# relay_board.net
KiCad netlist of a schematic drawn in EAGLE
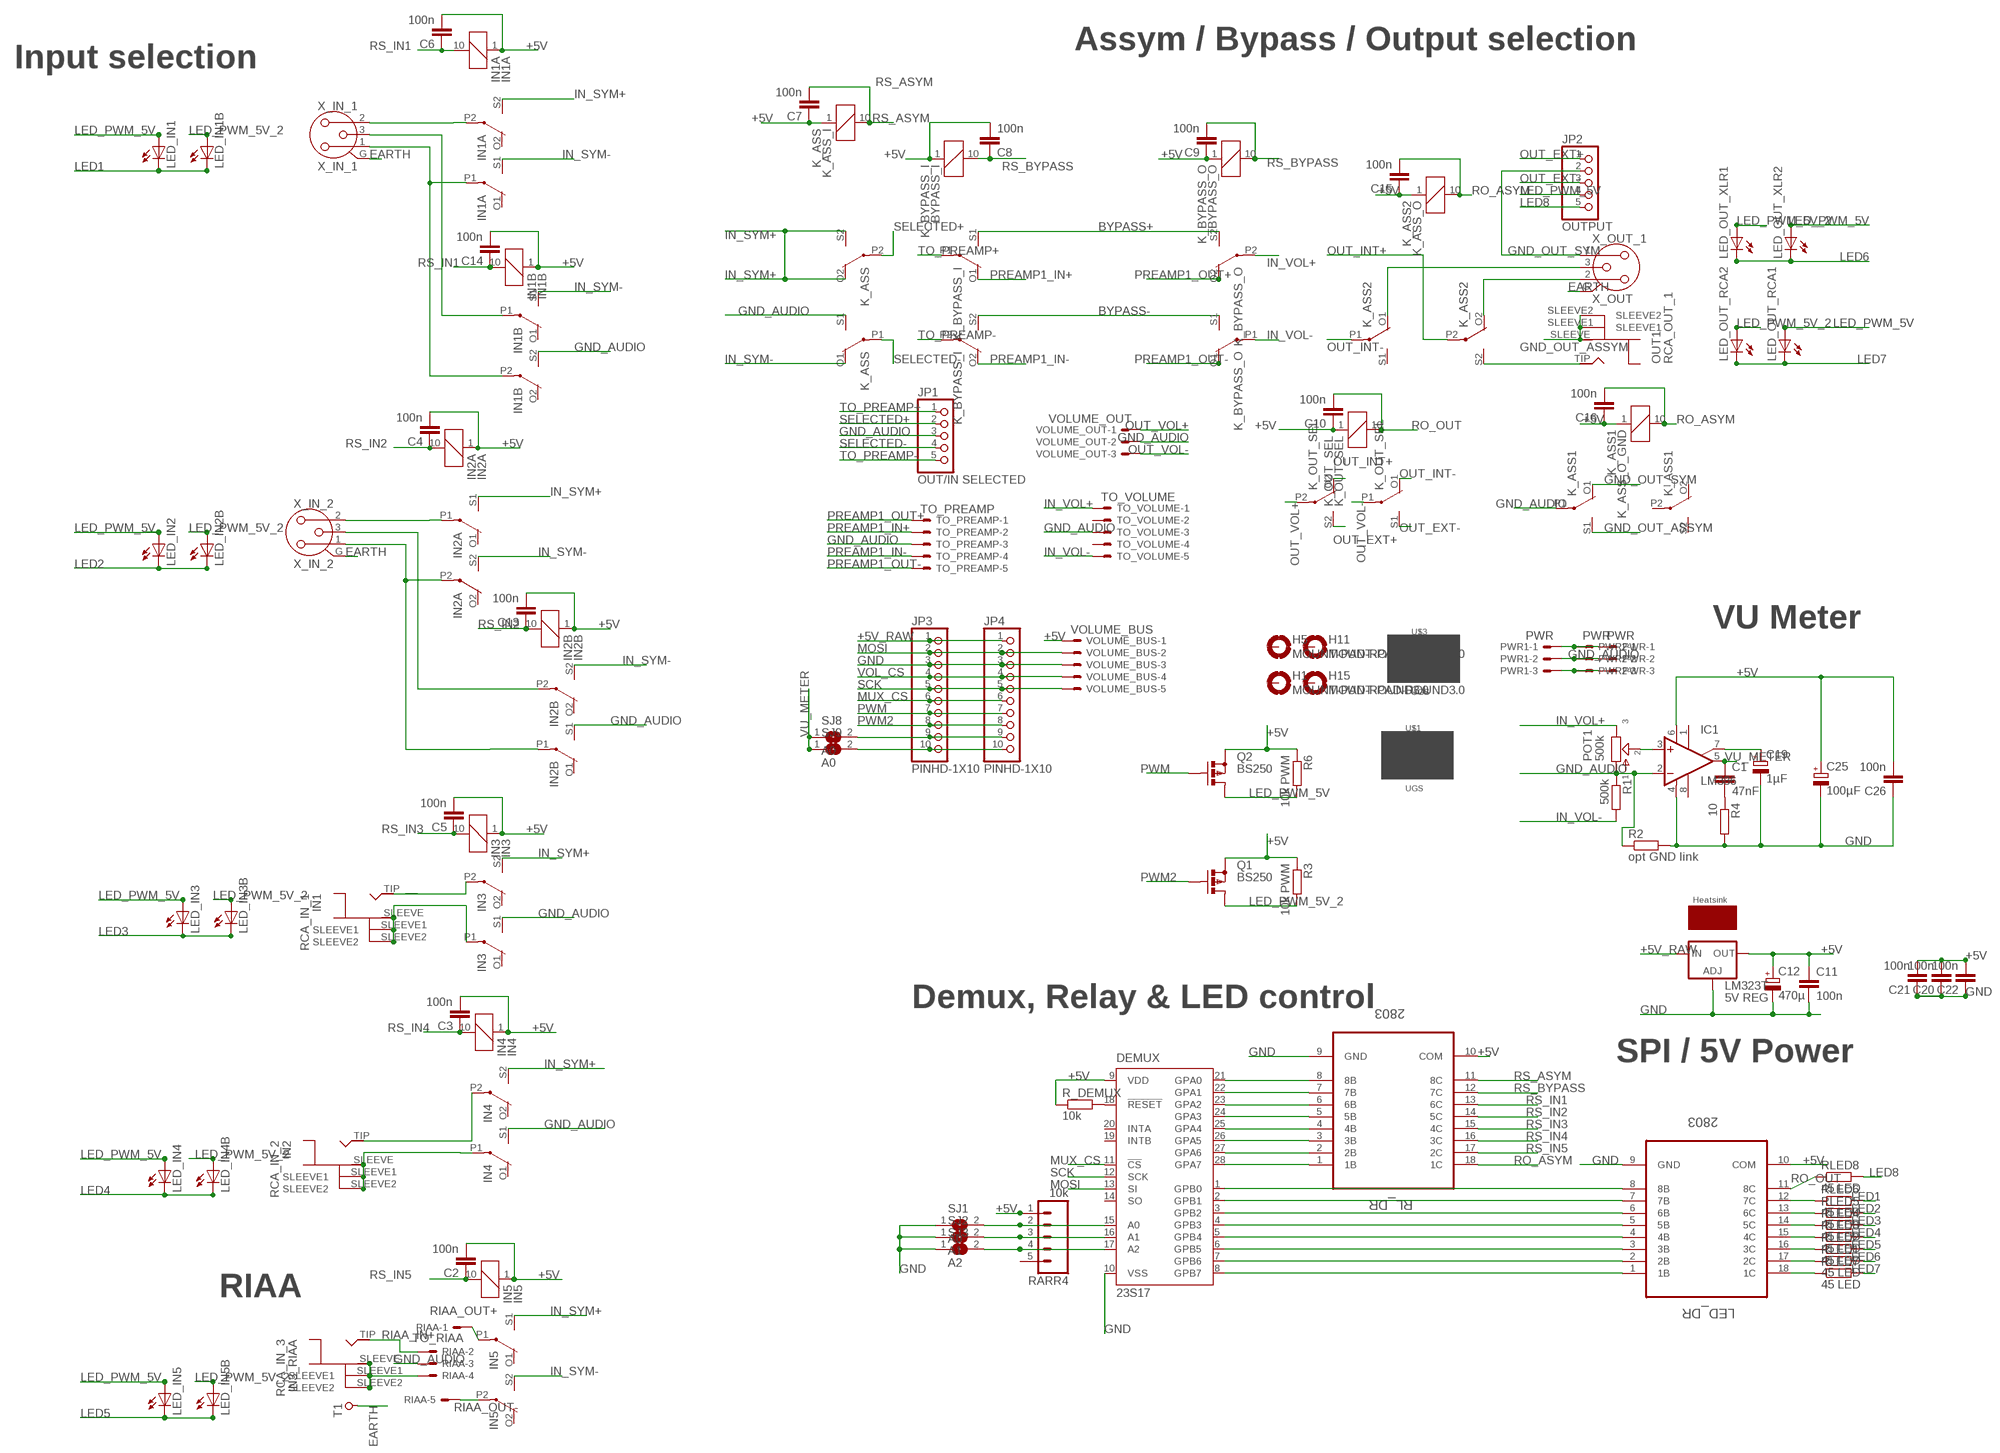
[diagram p0: schematic, sheet 1]

(export (version "E")
  (design (tool "Eeschema 10.0.6"))
  (components
    (comp (ref "C1")
      (value "47nF")
      (footprint "eagle-import:C5B3")
      (libsource (lib "eagle-import") (part "C5/3"))
    )
    (comp (ref "C2")
      (value "100n")
      (footprint "eagle-import:C050-025X075")
      (libsource (lib "eagle-import") (part "C-EU050-025X075"))
    )
    (comp (ref "C3")
      (value "100n")
      (footprint "eagle-import:C050-025X075")
      (libsource (lib "eagle-import") (part "C-EU050-025X075"))
    )
    (comp (ref "C4")
      (value "100n")
      (footprint "eagle-import:C050-025X075")
      (libsource (lib "eagle-import") (part "C-EU050-025X075"))
    )
    (comp (ref "C5")
      (value "100n")
      (footprint "eagle-import:C050-025X075")
      (libsource (lib "eagle-import") (part "C-EU050-025X075"))
    )
    (comp (ref "C6")
      (value "100n")
      (footprint "eagle-import:C050-025X075")
      (libsource (lib "eagle-import") (part "C-EU050-025X075"))
    )
    (comp (ref "C7")
      (value "100n")
      (footprint "eagle-import:C050-025X075")
      (libsource (lib "eagle-import") (part "C-EU050-025X075"))
    )
    (comp (ref "C8")
      (value "100n")
      (footprint "eagle-import:C050-025X075")
      (libsource (lib "eagle-import") (part "C-EU050-025X075"))
    )
    (comp (ref "C9")
      (value "100n")
      (footprint "eagle-import:C050-025X075")
      (libsource (lib "eagle-import") (part "C-EU050-025X075"))
    )
    (comp (ref "C10")
      (value "100n")
      (footprint "eagle-import:C050-025X075")
      (libsource (lib "eagle-import") (part "C-EU050-025X075"))
    )
    (comp (ref "C11")
      (value "100n")
      (footprint "eagle-import:C050-025X075")
      (libsource (lib "eagle-import") (part "C-EU050-025X075"))
    )
    (comp (ref "C12")
      (value "470µ")
      (footprint "eagle-import:E2,5-6")
      (libsource (lib "eagle-import") (part "CPOL-EUE2.5-6"))
    )
    (comp (ref "C13")
      (value "100n")
      (footprint "eagle-import:C050-025X075")
      (libsource (lib "eagle-import") (part "C-EU050-025X075"))
    )
    (comp (ref "C14")
      (value "100n")
      (footprint "eagle-import:C050-025X075")
      (libsource (lib "eagle-import") (part "C-EU050-025X075"))
    )
    (comp (ref "C15")
      (value "100n")
      (footprint "eagle-import:C050-025X075")
      (libsource (lib "eagle-import") (part "C-EU050-025X075"))
    )
    (comp (ref "C16")
      (value "100n")
      (footprint "eagle-import:C050-025X075")
      (libsource (lib "eagle-import") (part "C-EU050-025X075"))
    )
    (comp (ref "C19")
      (value "1µF")
      (footprint "eagle-import:E2,5-5")
      (libsource (lib "eagle-import") (part "CPOL-EUE2.5-5"))
    )
    (comp (ref "C20")
      (value "100n")
      (footprint "eagle-import:C050-025X075")
      (libsource (lib "eagle-import") (part "C-EU050-025X075"))
    )
    (comp (ref "C21")
      (value "100n")
      (footprint "eagle-import:C050-025X075")
      (libsource (lib "eagle-import") (part "C-EU050-025X075"))
    )
    (comp (ref "C22")
      (value "100n")
      (footprint "eagle-import:C050-025X075")
      (libsource (lib "eagle-import") (part "C-EU050-025X075"))
    )
    (comp (ref "C25")
      (value "100µF")
      (footprint "eagle-import:E5-6")
      (libsource (lib "eagle-import") (part "CPOL-EUE5-6"))
    )
    (comp (ref "C26")
      (value "100n")
      (footprint "eagle-import:C050-025X075")
      (libsource (lib "eagle-import") (part "C-EU050-025X075"))
    )
    (comp (ref "DEMUX")
      (value "23S17")
      (footprint "eagle-import:SO28W")
      (fields
        (field (name "MF") "MICROCHIP")
        (field (name "MPN") "MCP23S17-E/SO")
        (field (name "MPN_1") "MCP23S17-E/SO")
        (field (name "OC_FARNELL") "unknown")
        (field (name "OC_NEWARK") "31K2950")
      )
      (libsource (lib "eagle-import") (part "MCP23S17SO"))
    )
    (comp (ref "H1")
      (value "MOUNT-PAD-ROUND3.0")
      (footprint "eagle-import:3,0-PAD")
      (libsource (lib "eagle-import") (part "MOUNT-PAD-ROUND3.0"))
    )
    (comp (ref "H5")
      (value "MOUNT-PAD-ROUND3.0")
      (footprint "eagle-import:3,0-PAD")
      (libsource (lib "eagle-import") (part "MOUNT-PAD-ROUND3.0"))
    )
    (comp (ref "H11")
      (value "MOUNT-PAD-ROUND3.0")
      (footprint "eagle-import:3,0-PAD")
      (libsource (lib "eagle-import") (part "MOUNT-PAD-ROUND3.0"))
    )
    (comp (ref "H15")
      (value "MOUNT-PAD-ROUND3.0")
      (footprint "eagle-import:3,0-PAD")
      (libsource (lib "eagle-import") (part "MOUNT-PAD-ROUND3.0"))
    )
    (comp (ref "IC1")
      (value "LM386")
      (footprint "eagle-import:DIL08")
      (libsource (lib "eagle-import") (part "LM386"))
    )
    (comp (ref "IN1A")
      (value "IN1A")
      (footprint "eagle-import:G6H2-100")
      (libsource (lib "eagle-import") (part "G6H2-100"))
    )
    (comp (ref "IN1B")
      (value "IN1B")
      (footprint "eagle-import:G6H2-100")
      (fields (field (name "OC_FARNELL") "unknown") (field (name "OC_NEWARK") "unknown"))
      (libsource (lib "eagle-import") (part "G6H2-100"))
    )
    (comp (ref "IN2A")
      (value "IN2A")
      (footprint "eagle-import:G6H2-100")
      (libsource (lib "eagle-import") (part "G6H2-100"))
    )
    (comp (ref "IN2B")
      (value "IN2B")
      (footprint "eagle-import:G6H2-100")
      (fields (field (name "OC_FARNELL") "unknown") (field (name "OC_NEWARK") "unknown"))
      (libsource (lib "eagle-import") (part "G6H2-100"))
    )
    (comp (ref "IN3")
      (value "IN3")
      (footprint "eagle-import:G6H2-100")
      (fields (field (name "OC_FARNELL") "unknown") (field (name "OC_NEWARK") "unknown"))
      (libsource (lib "eagle-import") (part "G6H2-100"))
    )
    (comp (ref "IN4")
      (value "IN4")
      (footprint "eagle-import:G6H2-100")
      (fields (field (name "OC_FARNELL") "unknown") (field (name "OC_NEWARK") "unknown"))
      (libsource (lib "eagle-import") (part "G6H2-100"))
    )
    (comp (ref "IN5")
      (value "IN5")
      (footprint "eagle-import:G6H2-100")
      (libsource (lib "eagle-import") (part "G6H2-100"))
    )
    (comp (ref "JP1")
      (value "OUT/IN SELECTED")
      (footprint "eagle-import:1X05")
      (libsource (lib "eagle-import") (part "PINHD-1X5"))
    )
    (comp (ref "JP2")
      (value "OUTPUT")
      (footprint "eagle-import:1X05")
      (libsource (lib "eagle-import") (part "PINHD-1X5"))
    )
    (comp (ref "JP3")
      (value "PINHD-1X10")
      (footprint "eagle-import:1X10-BIG")
      (libsource (lib "eagle-import") (part "PINHD-1X10"))
    )
    (comp (ref "JP4")
      (value "PINHD-1X10")
      (footprint "eagle-import:1X10-BIG")
      (libsource (lib "eagle-import") (part "PINHD-1X10"))
    )
    (comp (ref "K_ASS")
      (value "K_ASS_I")
      (footprint "eagle-import:G6H2-100")
      (libsource (lib "eagle-import") (part "G6H2-100"))
    )
    (comp (ref "K_ASS1")
      (value "K_ASS_O_GND")
      (footprint "eagle-import:G6H2-100")
      (fields (field (name "OC_FARNELL") "unknown") (field (name "OC_NEWARK") "unknown"))
      (libsource (lib "eagle-import") (part "G6H2-100"))
    )
    (comp (ref "K_ASS2")
      (value "K_ASS_O")
      (footprint "eagle-import:G6H2-100")
      (fields (field (name "OC_FARNELL") "unknown") (field (name "OC_NEWARK") "unknown"))
      (libsource (lib "eagle-import") (part "G6H2-100"))
    )
    (comp (ref "K_BYPASS_I")
      (value "BYPASS_I")
      (footprint "eagle-import:G6H2-100")
      (libsource (lib "eagle-import") (part "G6H2-100"))
    )
    (comp (ref "K_BYPASS_O")
      (value "BYPASS_O")
      (footprint "eagle-import:G6H2-100")
      (libsource (lib "eagle-import") (part "G6H2-100"))
    )
    (comp (ref "K_OUT_SEL")
      (value "K_OUT_SEL")
      (footprint "eagle-import:G6H2-100")
      (fields (field (name "OC_FARNELL") "unknown") (field (name "OC_NEWARK") "unknown"))
      (libsource (lib "eagle-import") (part "G6H2-100"))
    )
    (comp (ref "LED_DR")
      (value "2803")
      (footprint "eagle-import:SOIC127P1030X265-18N")
      (fields
        (field (name "MPN") "ULN2803ADWR")
        (field (name "MPN_1") "ULN2803ADWR")
        (field (name "OC_FARNELL") "1652420")
        (field (name "OC_NEWARK") "87H4769")
        (field (name "PACKAGE") "SOIC-18")
        (field (name "SUPPLIER") "TEXAS INSTRUMENTS")
      )
      (libsource (lib "eagle-import") (part "ULN2803ADWR"))
    )
    (comp (ref "LED_IN1")
      (value "TLLG4400")
      (footprint "eagle-import:LED3MM")
      (fields (field (name "MF") "VISHAY SEMICONDUCTOR"))
      (libsource (lib "eagle-import") (part "TLLG4400"))
    )
    (comp (ref "LED_IN1B")
      (value "TLLG4400")
      (footprint "eagle-import:LED3MM")
      (fields
        (field (name "MF") "VISHAY SEMICONDUCTOR")
        (field (name "MF_1") "VISHAY SEMICONDUCTOR")
        (field (name "OC_FARNELL") "1612435")
      )
      (libsource (lib "eagle-import") (part "TLLG4400"))
    )
    (comp (ref "LED_IN2")
      (value "TLLG4400")
      (footprint "eagle-import:LED3MM")
      (fields (field (name "MF") "VISHAY SEMICONDUCTOR"))
      (libsource (lib "eagle-import") (part "TLLG4400"))
    )
    (comp (ref "LED_IN2B")
      (value "TLLG4400")
      (footprint "eagle-import:LED3MM")
      (fields
        (field (name "MF") "VISHAY SEMICONDUCTOR")
        (field (name "MF_1") "VISHAY SEMICONDUCTOR")
        (field (name "OC_FARNELL") "1612435")
      )
      (libsource (lib "eagle-import") (part "TLLG4400"))
    )
    (comp (ref "LED_IN3")
      (value "TLLG4400")
      (footprint "eagle-import:LED3MM")
      (fields (field (name "MF") "VISHAY SEMICONDUCTOR"))
      (libsource (lib "eagle-import") (part "TLLG4400"))
    )
    (comp (ref "LED_IN3B")
      (value "TLLG4400")
      (footprint "eagle-import:LED3MM")
      (fields
        (field (name "MF") "VISHAY SEMICONDUCTOR")
        (field (name "MF_1") "VISHAY SEMICONDUCTOR")
        (field (name "OC_FARNELL") "1612435")
      )
      (libsource (lib "eagle-import") (part "TLLG4400"))
    )
    (comp (ref "LED_IN4")
      (value "TLLG4400")
      (footprint "eagle-import:LED3MM")
      (fields (field (name "MF") "VISHAY SEMICONDUCTOR"))
      (libsource (lib "eagle-import") (part "TLLG4400"))
    )
    (comp (ref "LED_IN4B")
      (value "TLLG4400")
      (footprint "eagle-import:LED3MM")
      (fields
        (field (name "MF") "VISHAY SEMICONDUCTOR")
        (field (name "MF_1") "VISHAY SEMICONDUCTOR")
        (field (name "OC_FARNELL") "1612435")
      )
      (libsource (lib "eagle-import") (part "TLLG4400"))
    )
    (comp (ref "LED_IN5")
      (value "TLLG4400")
      (footprint "eagle-import:LED3MM")
      (fields (field (name "MF") "VISHAY SEMICONDUCTOR"))
      (libsource (lib "eagle-import") (part "TLLG4400"))
    )
    (comp (ref "LED_IN5B")
      (value "TLLG4400")
      (footprint "eagle-import:LED3MM")
      (fields
        (field (name "MF") "VISHAY SEMICONDUCTOR")
        (field (name "MF_1") "VISHAY SEMICONDUCTOR")
        (field (name "OC_FARNELL") "1612435")
      )
      (libsource (lib "eagle-import") (part "TLLG4400"))
    )
    (comp (ref "LED_OUT_RCA1")
      (value "TLLG4400")
      (footprint "eagle-import:LED3MM")
      (fields (field (name "MF") "VISHAY SEMICONDUCTOR"))
      (libsource (lib "eagle-import") (part "TLLG4400"))
    )
    (comp (ref "LED_OUT_RCA2")
      (value "TLLG4400")
      (footprint "eagle-import:LED3MM")
      (fields
        (field (name "MF") "VISHAY SEMICONDUCTOR")
        (field (name "MF_1") "VISHAY SEMICONDUCTOR")
        (field (name "OC_FARNELL") "1612435")
      )
      (libsource (lib "eagle-import") (part "TLLG4400"))
    )
    (comp (ref "LED_OUT_XLR1")
      (value "TLLG4400")
      (footprint "eagle-import:LED3MM")
      (fields
        (field (name "MF") "VISHAY SEMICONDUCTOR")
        (field (name "MF_1") "VISHAY SEMICONDUCTOR")
        (field (name "OC_FARNELL") "1612435")
      )
      (libsource (lib "eagle-import") (part "TLLG4400"))
    )
    (comp (ref "LED_OUT_XLR2")
      (value "TLLG4400")
      (footprint "eagle-import:LED3MM")
      (fields (field (name "MF") "VISHAY SEMICONDUCTOR"))
      (libsource (lib "eagle-import") (part "TLLG4400"))
    )
    (comp (ref "LM323T")
      (value "5V REG")
      (footprint "eagle-import:TO220S")
      (libsource (lib "eagle-import") (part "LM138-TSTO220S_IAO"))
    )
    (comp (ref "POT1")
      (value "500k")
      (footprint "eagle-import:B25P")
      (libsource (lib "eagle-import") (part "POT-EU25"))
    )
    (comp (ref "PWR")
      (value "PWR")
      (footprint "eagle-import:70543-03")
      (fields (field (name "OC_FARNELL") "unknown") (field (name "OC_NEWARK") "unknown"))
      (libsource (lib "eagle-import") (part "C-GRID-03-70543"))
    )
    (comp (ref "PWR1")
      (value "PWR")
      (footprint "eagle-import:70543-03")
      (fields (field (name "OC_FARNELL") "unknown") (field (name "OC_NEWARK") "unknown"))
      (libsource (lib "eagle-import") (part "C-GRID-03-70543"))
    )
    (comp (ref "PWR2")
      (value "PWR")
      (footprint "eagle-import:70543-03")
      (fields (field (name "OC_FARNELL") "unknown") (field (name "OC_NEWARK") "unknown"))
      (libsource (lib "eagle-import") (part "C-GRID-03-70543"))
    )
    (comp (ref "Q1")
      (value "BS250")
      (footprint "eagle-import:SOT54E")
      (libsource (lib "eagle-import") (part "BS250"))
    )
    (comp (ref "Q2")
      (value "BS250")
      (footprint "eagle-import:SOT54E")
      (libsource (lib "eagle-import") (part "BS250"))
    )
    (comp (ref "R1")
      (value "500k")
      (footprint "eagle-import:0207_7")
      (libsource (lib "eagle-import") (part "R-EU_0207/7"))
    )
    (comp (ref "R2")
      (value "opt GND link")
      (footprint "eagle-import:0207_10")
      (libsource (lib "eagle-import") (part "R-EU_0207/10"))
    )
    (comp (ref "R3")
      (value "10k PWM")
      (footprint "eagle-import:0207_10")
      (libsource (lib "eagle-import") (part "R-EU_0207/10"))
    )
    (comp (ref "R4")
      (value "10")
      (footprint "eagle-import:0207_10")
      (libsource (lib "eagle-import") (part "R-EU_0207/10"))
    )
    (comp (ref "R6")
      (value "10k PWM")
      (footprint "eagle-import:0207_10")
      (libsource (lib "eagle-import") (part "R-EU_0207/10"))
    )
    (comp (ref "RARR4")
      (value "10k")
      (footprint "eagle-import:1X05")
      (libsource (lib "eagle-import") (part "M05PTH"))
    )
    (comp (ref "RCA_IN_1")
      (value "IN1")
      (footprint "eagle-import:MONO_JACK")
      (libsource (lib "eagle-import") (part "MONO_JACKGAEL"))
    )
    (comp (ref "RCA_IN_2")
      (value "IN2")
      (footprint "eagle-import:MONO_JACK")
      (libsource (lib "eagle-import") (part "MONO_JACKGAEL"))
    )
    (comp (ref "RCA_IN_3")
      (value "IN3_RIAA")
      (footprint "eagle-import:MONO_JACK")
      (libsource (lib "eagle-import") (part "MONO_JACKGAEL"))
    )
    (comp (ref "RCA_OUT_1")
      (value "OUT1")
      (footprint "eagle-import:MONO_JACK")
      (libsource (lib "eagle-import") (part "MONO_JACKGAEL"))
    )
    (comp (ref "RIAA")
      (value "TO_RIAA")
      (footprint "eagle-import:70543-05")
      (libsource (lib "eagle-import") (part "C-GRID-05-70543"))
    )
    (comp (ref "RLED1")
      (value "45 LED")
      (footprint "eagle-import:0207_10")
      (libsource (lib "eagle-import") (part "R-EU_0207/10"))
    )
    (comp (ref "RLED2")
      (value "45 LED")
      (footprint "eagle-import:0207_10")
      (libsource (lib "eagle-import") (part "R-EU_0207/10"))
    )
    (comp (ref "RLED3")
      (value "45 LED")
      (footprint "eagle-import:0207_10")
      (libsource (lib "eagle-import") (part "R-EU_0207/10"))
    )
    (comp (ref "RLED4")
      (value "45 LED")
      (footprint "eagle-import:0207_10")
      (libsource (lib "eagle-import") (part "R-EU_0207/10"))
    )
    (comp (ref "RLED5")
      (value "45 LED")
      (footprint "eagle-import:0207_10")
      (libsource (lib "eagle-import") (part "R-EU_0207/10"))
    )
    (comp (ref "RLED6")
      (value "45 LED")
      (footprint "eagle-import:0207_10")
      (libsource (lib "eagle-import") (part "R-EU_0207/10"))
    )
    (comp (ref "RLED7")
      (value "45 LED")
      (footprint "eagle-import:0207_10")
      (libsource (lib "eagle-import") (part "R-EU_0207/10"))
    )
    (comp (ref "RLED8")
      (value "45 LED")
      (footprint "eagle-import:0207_10")
      (libsource (lib "eagle-import") (part "R-EU_0207/10"))
    )
    (comp (ref "RL_DR")
      (value "2803")
      (footprint "eagle-import:SOIC127P1030X265-18N")
      (fields (field (name "MPN") "ULN2803ADWR"))
      (libsource (lib "eagle-import") (part "ULN2803ADWR"))
    )
    (comp (ref "R_DEMUX")
      (value "10k")
      (footprint "eagle-import:RTH025W")
      (libsource (lib "eagle-import") (part "RESISTOR-PTH-0.4"))
    )
    (comp (ref "SJ1") (value "A0") (footprint "eagle-import:SJ") (libsource (lib "eagle-import") (part "SJ")))
    (comp (ref "SJ2") (value "A1") (footprint "eagle-import:SJ") (libsource (lib "eagle-import") (part "SJ")))
    (comp (ref "SJ3") (value "A2") (footprint "eagle-import:SJ") (libsource (lib "eagle-import") (part "SJ")))
    (comp (ref "SJ8") (value "A0") (footprint "eagle-import:SJ") (libsource (lib "eagle-import") (part "SJ")))
    (comp (ref "SJ9") (value "A0") (footprint "eagle-import:SJ") (libsource (lib "eagle-import") (part "SJ")))
    (comp (ref "T1")
      (value "PAD_TERMINAL-1.02MM_SQUARE")
      (footprint "eagle-import:CON_PAD_SQUARE_1.02MM")
      (libsource (lib "eagle-import") (part "PAD_TERMINAL-1.02MM_SQUARE"))
    )
    (comp (ref "TO_PREAMP")
      (value "TO_PREAMP")
      (footprint "eagle-import:70543-05")
      (libsource (lib "eagle-import") (part "C-GRID-05-70543"))
    )
    (comp (ref "TO_VOLUME")
      (value "TO_VOLUME")
      (footprint "eagle-import:70543-05")
      (fields (field (name "OC_FARNELL") "unknown") (field (name "OC_NEWARK") "unknown"))
      (libsource (lib "eagle-import") (part "C-GRID-05-70543"))
    )
    (comp (ref "U$1")
      (value "UGS")
      (footprint "eagle-import:UGS")
      (libsource (lib "eagle-import") (part "UGS"))
    )
    (comp (ref "U$3")
      (value "UGS")
      (footprint "eagle-import:UGS")
      (libsource (lib "eagle-import") (part "UGS"))
    )
    (comp (ref "U$4")
      (value "HEATSINK")
      (footprint "eagle-import:HEATSINK")
      (libsource (lib "eagle-import") (part "HEATSINK"))
    )
    (comp (ref "VOLUME_BUS")
      (value "VOLUME_BUS")
      (footprint "eagle-import:70543-05")
      (fields (field (name "OC_FARNELL") "unknown") (field (name "OC_NEWARK") "unknown"))
      (libsource (lib "eagle-import") (part "C-GRID-05-70543"))
    )
    (comp (ref "VOLUME_OUT")
      (value "VOLUME_OUT")
      (footprint "eagle-import:70543-03")
      (libsource (lib "eagle-import") (part "C-GRID-03-70543"))
    )
    (comp (ref "X_IN_1")
      (value "X_IN_1")
      (footprint "eagle-import:NC3FAH2")
      (fields (field (name "MPN") "NC3FAH2"))
      (libsource (lib "eagle-import") (part "NC3FAH2"))
    )
    (comp (ref "X_IN_2")
      (value "X_IN_2")
      (footprint "eagle-import:NC3FAH2")
      (fields (field (name "MPN") "NC3FAH2"))
      (libsource (lib "eagle-import") (part "NC3FAH2"))
    )
    (comp (ref "X_OUT_1")
      (value "X_OUT")
      (footprint "eagle-import:NC3MBH")
      (fields (field (name "MF") "NEUTRIK") (field (name "MPN") "NC3MBH"))
      (libsource (lib "eagle-import") (part "NC3MBH"))
    )
  )
  (nets
    (net (code "1") (name "/+5V") (class "Default")
      (node (ref "C10") (pin "1") (pinfunction "1_1") (pintype "passive"))
      (node (ref "C11") (pin "1") (pinfunction "1_1") (pintype "passive"))
      (node (ref "C12") (pin "+") (pinfunction "+_+") (pintype "passive"))
      (node (ref "C13") (pin "2") (pinfunction "2_2") (pintype "passive"))
      (node (ref "C14") (pin "2") (pinfunction "2_2") (pintype "passive"))
      (node (ref "C15") (pin "1") (pinfunction "1_1") (pintype "passive"))
      (node (ref "C16") (pin "1") (pinfunction "1_1") (pintype "passive"))
      (node (ref "C2") (pin "2") (pinfunction "2_2") (pintype "passive"))
      (node (ref "C20") (pin "2") (pinfunction "2_2") (pintype "passive"))
      (node (ref "C21") (pin "2") (pinfunction "2_2") (pintype "passive"))
      (node (ref "C22") (pin "2") (pinfunction "2_2") (pintype "passive"))
      (node (ref "C25") (pin "+") (pinfunction "+_+") (pintype "passive"))
      (node (ref "C26") (pin "2") (pinfunction "2_2") (pintype "passive"))
      (node (ref "C3") (pin "2") (pinfunction "2_2") (pintype "passive"))
      (node (ref "C4") (pin "2") (pinfunction "2_2") (pintype "passive"))
      (node (ref "C5") (pin "2") (pinfunction "2_2") (pintype "passive"))
      (node (ref "C6") (pin "2") (pinfunction "2_2") (pintype "passive"))
      (node (ref "C7") (pin "1") (pinfunction "1_1") (pintype "passive"))
      (node (ref "C8") (pin "2") (pinfunction "2_2") (pintype "passive"))
      (node (ref "C9") (pin "1") (pinfunction "1_1") (pintype "passive"))
      (node (ref "DEMUX") (pin "9") (pinfunction "VDD_9") (pintype "power_in"))
      (node (ref "IC1") (pin "6") (pinfunction "V+_6") (pintype "power_in"))
      (node (ref "IN1A") (pin "1") (pinfunction "1_1") (pintype "passive"))
      (node (ref "IN1B") (pin "1") (pinfunction "1_1") (pintype "passive"))
      (node (ref "IN2A") (pin "1") (pinfunction "1_1") (pintype "passive"))
      (node (ref "IN2B") (pin "1") (pinfunction "1_1") (pintype "passive"))
      (node (ref "IN3") (pin "1") (pinfunction "1_1") (pintype "passive"))
      (node (ref "IN4") (pin "1") (pinfunction "1_1") (pintype "passive"))
      (node (ref "IN5") (pin "1") (pinfunction "1_1") (pintype "passive"))
      (node (ref "K_ASS") (pin "1") (pinfunction "1_1") (pintype "passive"))
      (node (ref "K_ASS1") (pin "1") (pinfunction "1_1") (pintype "passive"))
      (node (ref "K_ASS2") (pin "1") (pinfunction "1_1") (pintype "passive"))
      (node (ref "K_BYPASS_I") (pin "1") (pinfunction "1_1") (pintype "passive"))
      (node (ref "K_BYPASS_O") (pin "1") (pinfunction "1_1") (pintype "passive"))
      (node (ref "K_OUT_SEL") (pin "1") (pinfunction "1_1") (pintype "passive"))
      (node (ref "LED_DR") (pin "10") (pinfunction "COM_10") (pintype "output"))
      (node (ref "LM323T") (pin "3") (pinfunction "OUT_3") (pintype "passive"))
      (node (ref "Q1") (pin "S") (pinfunction "S_S") (pintype "passive"))
      (node (ref "Q2") (pin "S") (pinfunction "S_S") (pintype "passive"))
      (node (ref "R3") (pin "1") (pinfunction "1_1") (pintype "passive"))
      (node (ref "R6") (pin "1") (pinfunction "1_1") (pintype "passive"))
      (node (ref "RARR4") (pin "1") (pinfunction "1_1") (pintype "passive"))
      (node (ref "RL_DR") (pin "10") (pinfunction "COM_10") (pintype "output"))
      (node (ref "R_DEMUX") (pin "1") (pinfunction "1_1") (pintype "passive"))
      (node (ref "VOLUME_BUS") (pin "1") (pinfunction "S_1") (pintype "passive"))
    )
    (net (code "2") (name "/+5V_RAW") (class "Default")
      (node (ref "JP3") (pin "1") (pinfunction "1_1") (pintype "passive"))
      (node (ref "JP4") (pin "1") (pinfunction "1_1") (pintype "passive"))
      (node (ref "LM323T") (pin "1") (pinfunction "IN_1") (pintype "input"))
    )
    (net (code "3") (name "/BYPASS+") (class "Default")
      (node (ref "K_BYPASS_I") (pin "S1") (pinfunction "S_S1") (pintype "passive"))
      (node (ref "K_BYPASS_O") (pin "S2") (pinfunction "S_S2") (pintype "passive"))
    )
    (net (code "4") (name "/BYPASS-") (class "Default")
      (node (ref "K_BYPASS_I") (pin "S2") (pinfunction "S_S2") (pintype "passive"))
      (node (ref "K_BYPASS_O") (pin "S1") (pinfunction "S_S1") (pintype "passive"))
    )
    (net (code "5") (name "/EARTH") (class "Default")
      (node (ref "T1") (pin "P") (pinfunction "P_P") (pintype "passive"))
      (node (ref "X_IN_1") (pin "G") (pinfunction "G_G") (pintype "passive"))
      (node (ref "X_IN_2") (pin "G") (pinfunction "G_G") (pintype "passive"))
      (node (ref "X_OUT_1") (pin "G") (pinfunction "G_G") (pintype "passive"))
    )
    (net (code "6") (name "/GND") (class "Default")
      (node (ref "C11") (pin "2") (pinfunction "2_2") (pintype "passive"))
      (node (ref "C12") (pin "-") (pinfunction "-_-") (pintype "passive"))
      (node (ref "C19") (pin "-") (pinfunction "-_-") (pintype "passive"))
      (node (ref "C20") (pin "1") (pinfunction "1_1") (pintype "passive"))
      (node (ref "C21") (pin "1") (pinfunction "1_1") (pintype "passive"))
      (node (ref "C22") (pin "1") (pinfunction "1_1") (pintype "passive"))
      (node (ref "C25") (pin "-") (pinfunction "-_-") (pintype "passive"))
      (node (ref "C26") (pin "1") (pinfunction "1_1") (pintype "passive"))
      (node (ref "DEMUX") (pin "10") (pinfunction "VSS_10") (pintype "power_in"))
      (node (ref "IC1") (pin "4") (pinfunction "V-_4") (pintype "power_in"))
      (node (ref "JP3") (pin "3") (pinfunction "3_3") (pintype "passive"))
      (node (ref "JP4") (pin "3") (pinfunction "3_3") (pintype "passive"))
      (node (ref "LED_DR") (pin "9") (pinfunction "GND_9") (pintype "passive"))
      (node (ref "LM323T") (pin "2") (pinfunction "ADJ_2") (pintype "input"))
      (node (ref "R2") (pin "2") (pinfunction "2_2") (pintype "passive"))
      (node (ref "R4") (pin "2") (pinfunction "2_2") (pintype "passive"))
      (node (ref "RL_DR") (pin "9") (pinfunction "GND_9") (pintype "passive"))
      (node (ref "SJ1") (pin "1") (pinfunction "1_1") (pintype "passive"))
      (node (ref "SJ2") (pin "1") (pinfunction "1_1") (pintype "passive"))
      (node (ref "SJ3") (pin "1") (pinfunction "1_1") (pintype "passive"))
      (node (ref "VOLUME_BUS") (pin "3") (pinfunction "S_3") (pintype "passive"))
    )
    (net (code "7") (name "/GND_AUDIO") (class "Default")
      (node (ref "IC1") (pin "2") (pinfunction "-IN_2") (pintype "input"))
      (node (ref "IN1B") (pin "S2") (pinfunction "S_S2") (pintype "passive"))
      (node (ref "IN2B") (pin "S1") (pinfunction "S_S1") (pintype "passive"))
      (node (ref "IN3") (pin "S1") (pinfunction "S_S1") (pintype "passive"))
      (node (ref "IN4") (pin "S1") (pinfunction "S_S1") (pintype "passive"))
      (node (ref "JP1") (pin "3") (pinfunction "3_3") (pintype "passive"))
      (node (ref "K_ASS") (pin "S1") (pinfunction "S_S1") (pintype "passive"))
      (node (ref "K_ASS1") (pin "P1") (pinfunction "P_P1") (pintype "passive"))
      (node (ref "POT1") (pin "1") (pinfunction "1_1") (pintype "passive"))
      (node (ref "PWR") (pin "2") (pinfunction "S_2") (pintype "passive"))
      (node (ref "PWR1") (pin "2") (pinfunction "S_2") (pintype "passive"))
      (node (ref "PWR2") (pin "2") (pinfunction "S_2") (pintype "passive"))
      (node (ref "R1") (pin "1") (pinfunction "1_1") (pintype "passive"))
      (node (ref "R2") (pin "1") (pinfunction "1_1") (pintype "passive"))
      (node (ref "RIAA") (pin "3") (pinfunction "S_3") (pintype "passive"))
      (node (ref "TO_PREAMP") (pin "3") (pinfunction "S_3") (pintype "passive"))
      (node (ref "TO_VOLUME") (pin "3") (pinfunction "S_3") (pintype "passive"))
      (node (ref "VOLUME_OUT") (pin "2") (pinfunction "S_2") (pintype "passive"))
    )
    (net (code "8") (name "/GND_OUT_ASSYM") (class "Default")
      (node (ref "K_ASS1") (pin "S1") (pinfunction "S_S1") (pintype "passive"))
      (node (ref "RCA_OUT_1") (pin "SLEEVE") (pinfunction "SLEEVE_SLEEVE") (pintype "passive"))
      (node (ref "RCA_OUT_1") (pin "SLEEVE1") (pinfunction "SLEEVE1_SLEEVE1") (pintype "passive"))
      (node (ref "RCA_OUT_1") (pin "SLEEVE2") (pinfunction "SLEEVE2_SLEEVE2") (pintype "passive"))
    )
    (net (code "9") (name "/GND_OUT_SYM") (class "Default")
      (node (ref "JP2") (pin "2") (pinfunction "2_2") (pintype "passive"))
      (node (ref "K_ASS1") (pin "O1") (pinfunction "O_O1") (pintype "passive"))
      (node (ref "X_OUT_1") (pin "1") (pinfunction "1_1") (pintype "passive"))
    )
    (net (code "10") (name "/IN_SYM+") (class "Default")
      (node (ref "IN1A") (pin "S2") (pinfunction "S_S2") (pintype "passive"))
      (node (ref "IN2A") (pin "S1") (pinfunction "S_S1") (pintype "passive"))
      (node (ref "IN3") (pin "S2") (pinfunction "S_S2") (pintype "passive"))
      (node (ref "IN4") (pin "S2") (pinfunction "S_S2") (pintype "passive"))
      (node (ref "IN5") (pin "S1") (pinfunction "S_S1") (pintype "passive"))
      (node (ref "K_ASS") (pin "O2") (pinfunction "O_O2") (pintype "passive"))
      (node (ref "K_ASS") (pin "S2") (pinfunction "S_S2") (pintype "passive"))
    )
    (net (code "11") (name "/IN_SYM-") (class "Default")
      (node (ref "IN1A") (pin "S1") (pinfunction "S_S1") (pintype "passive"))
      (node (ref "IN1B") (pin "S1") (pinfunction "S_S1") (pintype "passive"))
      (node (ref "IN2A") (pin "S2") (pinfunction "S_S2") (pintype "passive"))
      (node (ref "IN2B") (pin "S2") (pinfunction "S_S2") (pintype "passive"))
      (node (ref "IN5") (pin "S2") (pinfunction "S_S2") (pintype "passive"))
      (node (ref "K_ASS") (pin "O1") (pinfunction "O_O1") (pintype "passive"))
    )
    (net (code "12") (name "/IN_VOL+") (class "Default")
      (node (ref "K_BYPASS_O") (pin "P2") (pinfunction "P_P2") (pintype "passive"))
      (node (ref "POT1") (pin "3") (pinfunction "3_3") (pintype "passive"))
      (node (ref "TO_VOLUME") (pin "1") (pinfunction "S_1") (pintype "passive"))
    )
    (net (code "13") (name "/IN_VOL-") (class "Default")
      (node (ref "K_BYPASS_O") (pin "P1") (pinfunction "P_P1") (pintype "passive"))
      (node (ref "R1") (pin "2") (pinfunction "2_2") (pintype "passive"))
      (node (ref "TO_VOLUME") (pin "5") (pinfunction "S_5") (pintype "passive"))
    )
    (net (code "14") (name "/LED1") (class "Default")
      (node (ref "LED_IN1") (pin "K") (pinfunction "C_K") (pintype "passive"))
      (node (ref "LED_IN1B") (pin "K") (pinfunction "C_K") (pintype "passive"))
      (node (ref "RLED6") (pin "2") (pinfunction "2_2") (pintype "passive"))
    )
    (net (code "15") (name "/LED2") (class "Default")
      (node (ref "LED_IN2") (pin "K") (pinfunction "C_K") (pintype "passive"))
      (node (ref "LED_IN2B") (pin "K") (pinfunction "C_K") (pintype "passive"))
      (node (ref "RLED5") (pin "2") (pinfunction "2_2") (pintype "passive"))
    )
    (net (code "16") (name "/LED3") (class "Default")
      (node (ref "LED_IN3") (pin "K") (pinfunction "C_K") (pintype "passive"))
      (node (ref "LED_IN3B") (pin "K") (pinfunction "C_K") (pintype "passive"))
      (node (ref "RLED4") (pin "2") (pinfunction "2_2") (pintype "passive"))
    )
    (net (code "17") (name "/LED4") (class "Default")
      (node (ref "LED_IN4") (pin "K") (pinfunction "C_K") (pintype "passive"))
      (node (ref "LED_IN4B") (pin "K") (pinfunction "C_K") (pintype "passive"))
      (node (ref "RLED3") (pin "2") (pinfunction "2_2") (pintype "passive"))
    )
    (net (code "18") (name "/LED5") (class "Default")
      (node (ref "LED_IN5") (pin "K") (pinfunction "C_K") (pintype "passive"))
      (node (ref "LED_IN5B") (pin "K") (pinfunction "C_K") (pintype "passive"))
      (node (ref "RLED2") (pin "2") (pinfunction "2_2") (pintype "passive"))
    )
    (net (code "19") (name "/LED6") (class "Default")
      (node (ref "LED_OUT_XLR1") (pin "K") (pinfunction "C_K") (pintype "passive"))
      (node (ref "LED_OUT_XLR2") (pin "K") (pinfunction "C_K") (pintype "passive"))
      (node (ref "RLED1") (pin "2") (pinfunction "2_2") (pintype "passive"))
    )
    (net (code "20") (name "/LED7") (class "Default")
      (node (ref "LED_OUT_RCA1") (pin "K") (pinfunction "C_K") (pintype "passive"))
      (node (ref "LED_OUT_RCA2") (pin "K") (pinfunction "C_K") (pintype "passive"))
      (node (ref "RLED7") (pin "2") (pinfunction "2_2") (pintype "passive"))
    )
    (net (code "21") (name "/LED8") (class "Default")
      (node (ref "JP2") (pin "5") (pinfunction "5_5") (pintype "passive"))
      (node (ref "RLED8") (pin "2") (pinfunction "2_2") (pintype "passive"))
    )
    (net (code "22") (name "/LED_PWM_5V") (class "Default")
      (node (ref "JP2") (pin "4") (pinfunction "4_4") (pintype "passive"))
      (node (ref "LED_IN1") (pin "A") (pinfunction "A_A") (pintype "passive"))
      (node (ref "LED_IN2") (pin "A") (pinfunction "A_A") (pintype "passive"))
      (node (ref "LED_IN3") (pin "A") (pinfunction "A_A") (pintype "passive"))
      (node (ref "LED_IN4") (pin "A") (pinfunction "A_A") (pintype "passive"))
      (node (ref "LED_IN5") (pin "A") (pinfunction "A_A") (pintype "passive"))
      (node (ref "LED_OUT_RCA1") (pin "A") (pinfunction "A_A") (pintype "passive"))
      (node (ref "LED_OUT_XLR2") (pin "A") (pinfunction "A_A") (pintype "passive"))
      (node (ref "Q2") (pin "D") (pinfunction "D_D") (pintype "passive"))
      (node (ref "R6") (pin "2") (pinfunction "2_2") (pintype "passive"))
    )
    (net (code "23") (name "/LED_PWM_5V_2") (class "Default")
      (node (ref "LED_IN1B") (pin "A") (pinfunction "A_A") (pintype "passive"))
      (node (ref "LED_IN2B") (pin "A") (pinfunction "A_A") (pintype "passive"))
      (node (ref "LED_IN3B") (pin "A") (pinfunction "A_A") (pintype "passive"))
      (node (ref "LED_IN4B") (pin "A") (pinfunction "A_A") (pintype "passive"))
      (node (ref "LED_IN5B") (pin "A") (pinfunction "A_A") (pintype "passive"))
      (node (ref "LED_OUT_RCA2") (pin "A") (pinfunction "A_A") (pintype "passive"))
      (node (ref "LED_OUT_XLR1") (pin "A") (pinfunction "A_A") (pintype "passive"))
      (node (ref "Q1") (pin "D") (pinfunction "D_D") (pintype "passive"))
      (node (ref "R3") (pin "2") (pinfunction "2_2") (pintype "passive"))
    )
    (net (code "24") (name "/MOSI") (class "Default")
      (node (ref "DEMUX") (pin "13") (pinfunction "SI_13") (pintype "input"))
      (node (ref "JP3") (pin "2") (pinfunction "2_2") (pintype "passive"))
      (node (ref "JP4") (pin "2") (pinfunction "2_2") (pintype "passive"))
      (node (ref "VOLUME_BUS") (pin "2") (pinfunction "S_2") (pintype "passive"))
    )
    (net (code "25") (name "/MUX_CS") (class "Default")
      (node (ref "DEMUX") (pin "11") (pinfunction "~{CS}_11") (pintype "input"))
      (node (ref "JP3") (pin "6") (pinfunction "6_6") (pintype "passive"))
      (node (ref "JP4") (pin "6") (pinfunction "6_6") (pintype "passive"))
    )
    (net (code "26") (name "/OUT_EXT+") (class "Default")
      (node (ref "JP2") (pin "1") (pinfunction "1_1") (pintype "passive"))
      (node (ref "K_OUT_SEL") (pin "S2") (pinfunction "S_S2") (pintype "passive"))
    )
    (net (code "27") (name "/OUT_EXT-") (class "Default")
      (node (ref "JP2") (pin "3") (pinfunction "3_3") (pintype "passive"))
      (node (ref "K_OUT_SEL") (pin "S1") (pinfunction "S_S1") (pintype "passive"))
    )
    (net (code "28") (name "/OUT_INT+") (class "Default")
      (node (ref "K_ASS2") (pin "P2") (pinfunction "P_P2") (pintype "passive"))
      (node (ref "K_OUT_SEL") (pin "O2") (pinfunction "O_O2") (pintype "passive"))
    )
    (net (code "29") (name "/OUT_INT-") (class "Default")
      (node (ref "K_ASS2") (pin "P1") (pinfunction "P_P1") (pintype "passive"))
      (node (ref "K_OUT_SEL") (pin "O1") (pinfunction "O_O1") (pintype "passive"))
    )
    (net (code "30") (name "/OUT_VOL+") (class "Default")
      (node (ref "K_OUT_SEL") (pin "P2") (pinfunction "P_P2") (pintype "passive"))
      (node (ref "VOLUME_OUT") (pin "1") (pinfunction "S_1") (pintype "passive"))
    )
    (net (code "31") (name "/OUT_VOL-") (class "Default")
      (node (ref "K_OUT_SEL") (pin "P1") (pinfunction "P_P1") (pintype "passive"))
      (node (ref "VOLUME_OUT") (pin "3") (pinfunction "S_3") (pintype "passive"))
    )
    (net (code "32") (name "/PREAMP1_IN+") (class "Default")
      (node (ref "K_BYPASS_I") (pin "O1") (pinfunction "O_O1") (pintype "passive"))
      (node (ref "TO_PREAMP") (pin "2") (pinfunction "S_2") (pintype "passive"))
    )
    (net (code "33") (name "/PREAMP1_IN-") (class "Default")
      (node (ref "K_BYPASS_I") (pin "O2") (pinfunction "O_O2") (pintype "passive"))
      (node (ref "TO_PREAMP") (pin "4") (pinfunction "S_4") (pintype "passive"))
    )
    (net (code "34") (name "/PREAMP1_OUT+") (class "Default")
      (node (ref "K_BYPASS_O") (pin "O2") (pinfunction "O_O2") (pintype "passive"))
      (node (ref "TO_PREAMP") (pin "1") (pinfunction "S_1") (pintype "passive"))
    )
    (net (code "35") (name "/PREAMP1_OUT-") (class "Default")
      (node (ref "K_BYPASS_O") (pin "O1") (pinfunction "O_O1") (pintype "passive"))
      (node (ref "TO_PREAMP") (pin "5") (pinfunction "S_5") (pintype "passive"))
    )
    (net (code "36") (name "/PWM") (class "Default")
      (node (ref "JP3") (pin "7") (pinfunction "7_7") (pintype "passive"))
      (node (ref "JP4") (pin "7") (pinfunction "7_7") (pintype "passive"))
      (node (ref "Q2") (pin "G") (pinfunction "G_G") (pintype "passive"))
    )
    (net (code "37") (name "/PWM2") (class "Default")
      (node (ref "JP3") (pin "8") (pinfunction "8_8") (pintype "passive"))
      (node (ref "JP4") (pin "8") (pinfunction "8_8") (pintype "passive"))
      (node (ref "Q1") (pin "G") (pinfunction "G_G") (pintype "passive"))
    )
    (net (code "38") (name "/RIAA_IN+") (class "Default")
      (node (ref "RCA_IN_3") (pin "TIP") (pinfunction "TIP_TIP") (pintype "passive"))
      (node (ref "RIAA") (pin "2") (pinfunction "S_2") (pintype "passive"))
    )
    (net (code "39") (name "/RIAA_OUT+") (class "Default")
      (node (ref "IN5") (pin "P1") (pinfunction "P_P1") (pintype "passive"))
      (node (ref "RIAA") (pin "1") (pinfunction "S_1") (pintype "passive"))
    )
    (net (code "40") (name "/RIAA_OUT-") (class "Default")
      (node (ref "IN5") (pin "P2") (pinfunction "P_P2") (pintype "passive"))
      (node (ref "RIAA") (pin "5") (pinfunction "S_5") (pintype "passive"))
    )
    (net (code "41") (name "/RO_ASYM") (class "Default")
      (node (ref "C15") (pin "2") (pinfunction "2_2") (pintype "passive"))
      (node (ref "C16") (pin "2") (pinfunction "2_2") (pintype "passive"))
      (node (ref "K_ASS1") (pin "10") (pinfunction "2_10") (pintype "passive"))
      (node (ref "K_ASS2") (pin "10") (pinfunction "2_10") (pintype "passive"))
      (node (ref "RL_DR") (pin "18") (pinfunction "1C_18") (pintype "output"))
    )
    (net (code "42") (name "/RO_OUT") (class "Default")
      (node (ref "C10") (pin "2") (pinfunction "2_2") (pintype "passive"))
      (node (ref "K_OUT_SEL") (pin "10") (pinfunction "2_10") (pintype "passive"))
      (node (ref "LED_DR") (pin "11") (pinfunction "8C_11") (pintype "output"))
      (node (ref "RLED8") (pin "1") (pinfunction "1_1") (pintype "passive"))
    )
    (net (code "43") (name "/RS_ASYM") (class "Default")
      (node (ref "C7") (pin "2") (pinfunction "2_2") (pintype "passive"))
      (node (ref "K_ASS") (pin "10") (pinfunction "2_10") (pintype "passive"))
      (node (ref "RL_DR") (pin "11") (pinfunction "8C_11") (pintype "output"))
    )
    (net (code "44") (name "/RS_BYPASS") (class "Default")
      (node (ref "C8") (pin "1") (pinfunction "1_1") (pintype "passive"))
      (node (ref "C9") (pin "2") (pinfunction "2_2") (pintype "passive"))
      (node (ref "K_BYPASS_I") (pin "10") (pinfunction "2_10") (pintype "passive"))
      (node (ref "K_BYPASS_O") (pin "10") (pinfunction "2_10") (pintype "passive"))
      (node (ref "RL_DR") (pin "12") (pinfunction "7C_12") (pintype "output"))
    )
    (net (code "45") (name "/RS_IN1") (class "Default")
      (node (ref "C14") (pin "1") (pinfunction "1_1") (pintype "passive"))
      (node (ref "C6") (pin "1") (pinfunction "1_1") (pintype "passive"))
      (node (ref "IN1A") (pin "10") (pinfunction "2_10") (pintype "passive"))
      (node (ref "IN1B") (pin "10") (pinfunction "2_10") (pintype "passive"))
      (node (ref "RL_DR") (pin "13") (pinfunction "6C_13") (pintype "output"))
    )
    (net (code "46") (name "/RS_IN2") (class "Default")
      (node (ref "C13") (pin "1") (pinfunction "1_1") (pintype "passive"))
      (node (ref "C4") (pin "1") (pinfunction "1_1") (pintype "passive"))
      (node (ref "IN2A") (pin "10") (pinfunction "2_10") (pintype "passive"))
      (node (ref "IN2B") (pin "10") (pinfunction "2_10") (pintype "passive"))
      (node (ref "RL_DR") (pin "14") (pinfunction "5C_14") (pintype "output"))
    )
    (net (code "47") (name "/RS_IN3") (class "Default")
      (node (ref "C5") (pin "1") (pinfunction "1_1") (pintype "passive"))
      (node (ref "IN3") (pin "10") (pinfunction "2_10") (pintype "passive"))
      (node (ref "RL_DR") (pin "15") (pinfunction "4C_15") (pintype "output"))
    )
    (net (code "48") (name "/RS_IN4") (class "Default")
      (node (ref "C3") (pin "1") (pinfunction "1_1") (pintype "passive"))
      (node (ref "IN4") (pin "10") (pinfunction "2_10") (pintype "passive"))
      (node (ref "RL_DR") (pin "16") (pinfunction "3C_16") (pintype "output"))
    )
    (net (code "49") (name "/RS_IN5") (class "Default")
      (node (ref "C2") (pin "1") (pinfunction "1_1") (pintype "passive"))
      (node (ref "IN5") (pin "10") (pinfunction "2_10") (pintype "passive"))
      (node (ref "RL_DR") (pin "17") (pinfunction "2C_17") (pintype "output"))
    )
    (net (code "50") (name "/SCK") (class "Default")
      (node (ref "DEMUX") (pin "12") (pinfunction "SCK_12") (pintype "input"))
      (node (ref "JP3") (pin "5") (pinfunction "5_5") (pintype "passive"))
      (node (ref "JP4") (pin "5") (pinfunction "5_5") (pintype "passive"))
      (node (ref "VOLUME_BUS") (pin "5") (pinfunction "S_5") (pintype "passive"))
    )
    (net (code "51") (name "/SELECTED+") (class "Default")
      (node (ref "JP1") (pin "2") (pinfunction "2_2") (pintype "passive"))
      (node (ref "K_ASS") (pin "P2") (pinfunction "P_P2") (pintype "passive"))
    )
    (net (code "52") (name "/SELECTED-") (class "Default")
      (node (ref "JP1") (pin "4") (pinfunction "4_4") (pintype "passive"))
      (node (ref "K_ASS") (pin "P1") (pinfunction "P_P1") (pintype "passive"))
    )
    (net (code "53") (name "/TO_PREAMP+") (class "Default")
      (node (ref "JP1") (pin "1") (pinfunction "1_1") (pintype "passive"))
      (node (ref "K_BYPASS_I") (pin "P1") (pinfunction "P_P1") (pintype "passive"))
    )
    (net (code "54") (name "/TO_PREAMP-") (class "Default")
      (node (ref "JP1") (pin "5") (pinfunction "5_5") (pintype "passive"))
      (node (ref "K_BYPASS_I") (pin "P2") (pinfunction "P_P2") (pintype "passive"))
    )
    (net (code "55") (name "/VOL_CS") (class "Default")
      (node (ref "JP3") (pin "4") (pinfunction "4_4") (pintype "passive"))
      (node (ref "JP4") (pin "4") (pinfunction "4_4") (pintype "passive"))
      (node (ref "VOLUME_BUS") (pin "4") (pinfunction "S_4") (pintype "passive"))
    )
    (net (code "56") (name "/VU_METER") (class "Default")
      (node (ref "C1") (pin "1") (pinfunction "1_1") (pintype "passive"))
      (node (ref "IC1") (pin "5") (pinfunction "OUT_5") (pintype "output"))
      (node (ref "SJ8") (pin "1") (pinfunction "1_1") (pintype "passive"))
      (node (ref "SJ9") (pin "1") (pinfunction "1_1") (pintype "passive"))
    )
    (net (code "57") (name "Net-(C1-Pad2)") (class "Default")
      (node (ref "C1") (pin "2") (pinfunction "2_2") (pintype "passive"))
      (node (ref "R4") (pin "1") (pinfunction "1_1") (pintype "passive"))
    )
    (net (code "58") (name "Net-(DEMUX-A0)") (class "Default")
      (node (ref "DEMUX") (pin "15") (pinfunction "A0_15") (pintype "input"))
      (node (ref "RARR4") (pin "2") (pinfunction "2_2") (pintype "passive"))
      (node (ref "SJ1") (pin "2") (pinfunction "2_2") (pintype "passive"))
    )
    (net (code "59") (name "Net-(DEMUX-A1)") (class "Default")
      (node (ref "DEMUX") (pin "16") (pinfunction "A1_16") (pintype "input"))
      (node (ref "RARR4") (pin "3") (pinfunction "3_3") (pintype "passive"))
      (node (ref "SJ2") (pin "2") (pinfunction "2_2") (pintype "passive"))
    )
    (net (code "60") (name "Net-(DEMUX-A2)") (class "Default")
      (node (ref "DEMUX") (pin "17") (pinfunction "A2_17") (pintype "input"))
      (node (ref "RARR4") (pin "4") (pinfunction "4_4") (pintype "passive"))
      (node (ref "SJ3") (pin "2") (pinfunction "2_2") (pintype "passive"))
    )
    (net (code "61") (name "Net-(DEMUX-GPA0)") (class "Default")
      (node (ref "DEMUX") (pin "21") (pinfunction "GPA0_21") (pintype "bidirectional"))
      (node (ref "RL_DR") (pin "8") (pinfunction "8B_8") (pintype "input"))
    )
    (net (code "62") (name "Net-(DEMUX-GPA1)") (class "Default")
      (node (ref "DEMUX") (pin "22") (pinfunction "GPA1_22") (pintype "bidirectional"))
      (node (ref "RL_DR") (pin "7") (pinfunction "7B_7") (pintype "input"))
    )
    (net (code "63") (name "Net-(DEMUX-GPA2)") (class "Default")
      (node (ref "DEMUX") (pin "23") (pinfunction "GPA2_23") (pintype "bidirectional"))
      (node (ref "RL_DR") (pin "6") (pinfunction "6B_6") (pintype "input"))
    )
    (net (code "64") (name "Net-(DEMUX-GPA3)") (class "Default")
      (node (ref "DEMUX") (pin "24") (pinfunction "GPA3_24") (pintype "bidirectional"))
      (node (ref "RL_DR") (pin "5") (pinfunction "5B_5") (pintype "input"))
    )
    (net (code "65") (name "Net-(DEMUX-GPA4)") (class "Default")
      (node (ref "DEMUX") (pin "25") (pinfunction "GPA4_25") (pintype "bidirectional"))
      (node (ref "RL_DR") (pin "4") (pinfunction "4B_4") (pintype "input"))
    )
    (net (code "66") (name "Net-(DEMUX-GPA5)") (class "Default")
      (node (ref "DEMUX") (pin "26") (pinfunction "GPA5_26") (pintype "bidirectional"))
      (node (ref "RL_DR") (pin "3") (pinfunction "3B_3") (pintype "input"))
    )
    (net (code "67") (name "Net-(DEMUX-GPA6)") (class "Default")
      (node (ref "DEMUX") (pin "27") (pinfunction "GPA6_27") (pintype "bidirectional"))
      (node (ref "RL_DR") (pin "2") (pinfunction "2B_2") (pintype "input"))
    )
    (net (code "68") (name "Net-(DEMUX-GPA7)") (class "Default")
      (node (ref "DEMUX") (pin "28") (pinfunction "GPA7_28") (pintype "bidirectional"))
      (node (ref "RL_DR") (pin "1") (pinfunction "1B_1") (pintype "input"))
    )
    (net (code "69") (name "Net-(DEMUX-GPB0)") (class "Default")
      (node (ref "DEMUX") (pin "1") (pinfunction "GPB0_1") (pintype "bidirectional"))
      (node (ref "LED_DR") (pin "8") (pinfunction "8B_8") (pintype "input"))
    )
    (net (code "70") (name "Net-(DEMUX-GPB1)") (class "Default")
      (node (ref "DEMUX") (pin "2") (pinfunction "GPB1_2") (pintype "bidirectional"))
      (node (ref "LED_DR") (pin "7") (pinfunction "7B_7") (pintype "input"))
    )
    (net (code "71") (name "Net-(DEMUX-GPB2)") (class "Default")
      (node (ref "DEMUX") (pin "3") (pinfunction "GPB2_3") (pintype "bidirectional"))
      (node (ref "LED_DR") (pin "6") (pinfunction "6B_6") (pintype "input"))
    )
    (net (code "72") (name "Net-(DEMUX-GPB3)") (class "Default")
      (node (ref "DEMUX") (pin "4") (pinfunction "GPB3_4") (pintype "bidirectional"))
      (node (ref "LED_DR") (pin "5") (pinfunction "5B_5") (pintype "input"))
    )
    (net (code "73") (name "Net-(DEMUX-GPB4)") (class "Default")
      (node (ref "DEMUX") (pin "5") (pinfunction "GPB4_5") (pintype "bidirectional"))
      (node (ref "LED_DR") (pin "4") (pinfunction "4B_4") (pintype "input"))
    )
    (net (code "74") (name "Net-(DEMUX-GPB5)") (class "Default")
      (node (ref "DEMUX") (pin "6") (pinfunction "GPB5_6") (pintype "bidirectional"))
      (node (ref "LED_DR") (pin "3") (pinfunction "3B_3") (pintype "input"))
    )
    (net (code "75") (name "Net-(DEMUX-GPB6)") (class "Default")
      (node (ref "DEMUX") (pin "7") (pinfunction "GPB6_7") (pintype "bidirectional"))
      (node (ref "LED_DR") (pin "2") (pinfunction "2B_2") (pintype "input"))
    )
    (net (code "76") (name "Net-(DEMUX-GPB7)") (class "Default")
      (node (ref "DEMUX") (pin "8") (pinfunction "GPB7_8") (pintype "bidirectional"))
      (node (ref "LED_DR") (pin "1") (pinfunction "1B_1") (pintype "input"))
    )
    (net (code "77") (name "Net-(DEMUX-~{RESET})") (class "Default")
      (node (ref "DEMUX") (pin "18") (pinfunction "~{RESET}_18") (pintype "input"))
      (node (ref "R_DEMUX") (pin "2") (pinfunction "2_2") (pintype "passive"))
    )
    (net (code "78") (name "Net-(IC1-+IN)") (class "Default")
      (node (ref "IC1") (pin "3") (pinfunction "+IN_3") (pintype "input"))
      (node (ref "POT1") (pin "2") (pinfunction "2_2") (pintype "passive"))
    )
    (net (code "79") (name "Net-(IC1-BYPASS)") (class "Default")
      (node (ref "C19") (pin "+") (pinfunction "+_+") (pintype "passive"))
      (node (ref "IC1") (pin "7") (pinfunction "BYPASS_7") (pintype "passive"))
    )
    (net (code "80") (name "Net-(IN1AB-P)") (class "Default")
      (node (ref "IN1A") (pin "P1") (pinfunction "P_P1") (pintype "passive"))
      (node (ref "IN1B") (pin "P2") (pinfunction "P_P2") (pintype "passive"))
      (node (ref "X_IN_1") (pin "1") (pinfunction "2_1") (pintype "passive"))
    )
    (net (code "81") (name "Net-(IN1AC-P)") (class "Default")
      (node (ref "IN1A") (pin "P2") (pinfunction "P_P2") (pintype "passive"))
      (node (ref "X_IN_1") (pin "2") (pinfunction "1_2") (pintype "passive"))
    )
    (net (code "82") (name "Net-(IN1BB-P)") (class "Default")
      (node (ref "IN1B") (pin "P1") (pinfunction "P_P1") (pintype "passive"))
      (node (ref "X_IN_1") (pin "3") (pinfunction "3_3") (pintype "passive"))
    )
    (net (code "83") (name "Net-(IN2AB-P)") (class "Default")
      (node (ref "IN2A") (pin "P1") (pinfunction "P_P1") (pintype "passive"))
      (node (ref "X_IN_2") (pin "2") (pinfunction "1_2") (pintype "passive"))
    )
    (net (code "84") (name "Net-(IN2AC-P)") (class "Default")
      (node (ref "IN2A") (pin "P2") (pinfunction "P_P2") (pintype "passive"))
      (node (ref "IN2B") (pin "P1") (pinfunction "P_P1") (pintype "passive"))
      (node (ref "X_IN_2") (pin "1") (pinfunction "2_1") (pintype "passive"))
    )
    (net (code "85") (name "Net-(IN2BC-P)") (class "Default")
      (node (ref "IN2B") (pin "P2") (pinfunction "P_P2") (pintype "passive"))
      (node (ref "X_IN_2") (pin "3") (pinfunction "3_3") (pintype "passive"))
    )
    (net (code "86") (name "Net-(IN3B-P)") (class "Default")
      (node (ref "IN3") (pin "P1") (pinfunction "P_P1") (pintype "passive"))
      (node (ref "RCA_IN_1") (pin "SLEEVE") (pinfunction "SLEEVE_SLEEVE") (pintype "passive"))
      (node (ref "RCA_IN_1") (pin "SLEEVE1") (pinfunction "SLEEVE1_SLEEVE1") (pintype "passive"))
      (node (ref "RCA_IN_1") (pin "SLEEVE2") (pinfunction "SLEEVE2_SLEEVE2") (pintype "passive"))
    )
    (net (code "87") (name "Net-(IN3C-P)") (class "Default")
      (node (ref "IN3") (pin "P2") (pinfunction "P_P2") (pintype "passive"))
      (node (ref "RCA_IN_1") (pin "TIP") (pinfunction "TIP_TIP") (pintype "passive"))
    )
    (net (code "88") (name "Net-(IN4B-P)") (class "Default")
      (node (ref "IN4") (pin "P1") (pinfunction "P_P1") (pintype "passive"))
      (node (ref "RCA_IN_2") (pin "SLEEVE") (pinfunction "SLEEVE_SLEEVE") (pintype "passive"))
      (node (ref "RCA_IN_2") (pin "SLEEVE1") (pinfunction "SLEEVE1_SLEEVE1") (pintype "passive"))
      (node (ref "RCA_IN_2") (pin "SLEEVE2") (pinfunction "SLEEVE2_SLEEVE2") (pintype "passive"))
    )
    (net (code "89") (name "Net-(IN4C-P)") (class "Default")
      (node (ref "IN4") (pin "P2") (pinfunction "P_P2") (pintype "passive"))
      (node (ref "RCA_IN_2") (pin "TIP") (pinfunction "TIP_TIP") (pintype "passive"))
    )
    (net (code "90") (name "Net-(JP3-Pad9)") (class "Default")
      (node (ref "JP3") (pin "9") (pinfunction "9_9") (pintype "passive"))
      (node (ref "JP4") (pin "9") (pinfunction "9_9") (pintype "passive"))
      (node (ref "SJ8") (pin "2") (pinfunction "2_2") (pintype "passive"))
    )
    (net (code "91") (name "Net-(JP3-Pad10)") (class "Default")
      (node (ref "JP3") (pin "10") (pinfunction "10_10") (pintype "passive"))
      (node (ref "JP4") (pin "10") (pinfunction "10_10") (pintype "passive"))
      (node (ref "SJ9") (pin "2") (pinfunction "2_2") (pintype "passive"))
    )
    (net (code "92") (name "Net-(K_ASS2B-O)") (class "Default")
      (node (ref "K_ASS2") (pin "O1") (pinfunction "O_O1") (pintype "passive"))
      (node (ref "X_OUT_1") (pin "3") (pinfunction "3_3") (pintype "passive"))
    )
    (net (code "93") (name "Net-(K_ASS2C-O)") (class "Default")
      (node (ref "K_ASS2") (pin "O2") (pinfunction "O_O2") (pintype "passive"))
      (node (ref "X_OUT_1") (pin "2") (pinfunction "2_2") (pintype "passive"))
    )
    (net (code "94") (name "Net-(K_ASS2C-S)") (class "Default")
      (node (ref "K_ASS2") (pin "S2") (pinfunction "S_S2") (pintype "passive"))
      (node (ref "RCA_OUT_1") (pin "TIP") (pinfunction "TIP_TIP") (pintype "passive"))
    )
    (net (code "95") (name "Net-(LED_DR-1C)") (class "Default")
      (node (ref "LED_DR") (pin "18") (pinfunction "1C_18") (pintype "output"))
      (node (ref "RLED7") (pin "1") (pinfunction "1_1") (pintype "passive"))
    )
    (net (code "96") (name "Net-(LED_DR-2C)") (class "Default")
      (node (ref "LED_DR") (pin "17") (pinfunction "2C_17") (pintype "output"))
      (node (ref "RLED1") (pin "1") (pinfunction "1_1") (pintype "passive"))
    )
    (net (code "97") (name "Net-(LED_DR-3C)") (class "Default")
      (node (ref "LED_DR") (pin "16") (pinfunction "3C_16") (pintype "output"))
      (node (ref "RLED2") (pin "1") (pinfunction "1_1") (pintype "passive"))
    )
    (net (code "98") (name "Net-(LED_DR-4C)") (class "Default")
      (node (ref "LED_DR") (pin "15") (pinfunction "4C_15") (pintype "output"))
      (node (ref "RLED3") (pin "1") (pinfunction "1_1") (pintype "passive"))
    )
    (net (code "99") (name "Net-(LED_DR-5C)") (class "Default")
      (node (ref "LED_DR") (pin "14") (pinfunction "5C_14") (pintype "output"))
      (node (ref "RLED4") (pin "1") (pinfunction "1_1") (pintype "passive"))
    )
    (net (code "100") (name "Net-(LED_DR-6C)") (class "Default")
      (node (ref "LED_DR") (pin "13") (pinfunction "6C_13") (pintype "output"))
      (node (ref "RLED5") (pin "1") (pinfunction "1_1") (pintype "passive"))
    )
    (net (code "101") (name "Net-(LED_DR-7C)") (class "Default")
      (node (ref "LED_DR") (pin "12") (pinfunction "7C_12") (pintype "output"))
      (node (ref "RLED6") (pin "1") (pinfunction "1_1") (pintype "passive"))
    )
    (net (code "102") (name "Net-(PWR1A-S)") (class "Default")
      (node (ref "PWR") (pin "1") (pinfunction "S_1") (pintype "passive"))
      (node (ref "PWR1") (pin "1") (pinfunction "S_1") (pintype "passive"))
      (node (ref "PWR2") (pin "1") (pinfunction "S_1") (pintype "passive"))
    )
    (net (code "103") (name "Net-(PWR1C-S)") (class "Default")
      (node (ref "PWR") (pin "3") (pinfunction "S_3") (pintype "passive"))
      (node (ref "PWR1") (pin "3") (pinfunction "S_3") (pintype "passive"))
      (node (ref "PWR2") (pin "3") (pinfunction "S_3") (pintype "passive"))
    )
    (net (code "104") (name "Net-(RIAAD-S)") (class "Default")
      (node (ref "RCA_IN_3") (pin "SLEEVE") (pinfunction "SLEEVE_SLEEVE") (pintype "passive"))
      (node (ref "RCA_IN_3") (pin "SLEEVE1") (pinfunction "SLEEVE1_SLEEVE1") (pintype "passive"))
      (node (ref "RCA_IN_3") (pin "SLEEVE2") (pinfunction "SLEEVE2_SLEEVE2") (pintype "passive"))
      (node (ref "RIAA") (pin "4") (pinfunction "S_4") (pintype "passive"))
    )
    (net (code "105") (name "unconnected-(DEMUX-INTA-Pad20)") (class "Default")
      (node (ref "DEMUX") (pin "20") (pinfunction "INTA_20") (pintype "output"))
    )
    (net (code "106") (name "unconnected-(DEMUX-INTB-Pad19)") (class "Default")
      (node (ref "DEMUX") (pin "19") (pinfunction "INTB_19") (pintype "output"))
    )
    (net (code "107") (name "unconnected-(DEMUX-SO-Pad14)") (class "Default")
      (node (ref "DEMUX") (pin "14") (pinfunction "SO_14") (pintype "output"))
    )
    (net (code "108") (name "unconnected-(H1-MOUNT-PadB3,0)") (class "Default")
      (node (ref "H1") (pin "B3,0") (pinfunction "MOUNT_B3,0") (pintype "passive"))
    )
    (net (code "109") (name "unconnected-(H5-MOUNT-PadB3,0)") (class "Default")
      (node (ref "H5") (pin "B3,0") (pinfunction "MOUNT_B3,0") (pintype "passive"))
    )
    (net (code "110") (name "unconnected-(H11-MOUNT-PadB3,0)") (class "Default")
      (node (ref "H11") (pin "B3,0") (pinfunction "MOUNT_B3,0") (pintype "passive"))
    )
    (net (code "111") (name "unconnected-(H15-MOUNT-PadB3,0)") (class "Default")
      (node (ref "H15") (pin "B3,0") (pinfunction "MOUNT_B3,0") (pintype "passive"))
    )
    (net (code "112") (name "unconnected-(IC1-GAIN1-Pad1)") (class "Default")
      (node (ref "IC1") (pin "1") (pinfunction "GAIN1_1") (pintype "passive"))
    )
    (net (code "113") (name "unconnected-(IC1-GAIN2-Pad8)") (class "Default")
      (node (ref "IC1") (pin "8") (pinfunction "GAIN2_8") (pintype "passive"))
    )
    (net (code "114") (name "unconnected-(IN1AB-O-PadO1)") (class "Default")
      (node (ref "IN1A") (pin "O1") (pinfunction "O_O1") (pintype "passive"))
    )
    (net (code "115") (name "unconnected-(IN1AC-O-PadO2)") (class "Default")
      (node (ref "IN1A") (pin "O2") (pinfunction "O_O2") (pintype "passive"))
    )
    (net (code "116") (name "unconnected-(IN1BB-O-PadO1)") (class "Default")
      (node (ref "IN1B") (pin "O1") (pinfunction "O_O1") (pintype "passive"))
    )
    (net (code "117") (name "unconnected-(IN1BC-O-PadO2)") (class "Default")
      (node (ref "IN1B") (pin "O2") (pinfunction "O_O2") (pintype "passive"))
    )
    (net (code "118") (name "unconnected-(IN2AB-O-PadO1)") (class "Default")
      (node (ref "IN2A") (pin "O1") (pinfunction "O_O1") (pintype "passive"))
    )
    (net (code "119") (name "unconnected-(IN2AC-O-PadO2)") (class "Default")
      (node (ref "IN2A") (pin "O2") (pinfunction "O_O2") (pintype "passive"))
    )
    (net (code "120") (name "unconnected-(IN2BB-O-PadO1)") (class "Default")
      (node (ref "IN2B") (pin "O1") (pinfunction "O_O1") (pintype "passive"))
    )
    (net (code "121") (name "unconnected-(IN2BC-O-PadO2)") (class "Default")
      (node (ref "IN2B") (pin "O2") (pinfunction "O_O2") (pintype "passive"))
    )
    (net (code "122") (name "unconnected-(IN3B-O-PadO1)") (class "Default")
      (node (ref "IN3") (pin "O1") (pinfunction "O_O1") (pintype "passive"))
    )
    (net (code "123") (name "unconnected-(IN3C-O-PadO2)") (class "Default")
      (node (ref "IN3") (pin "O2") (pinfunction "O_O2") (pintype "passive"))
    )
    (net (code "124") (name "unconnected-(IN4B-O-PadO1)") (class "Default")
      (node (ref "IN4") (pin "O1") (pinfunction "O_O1") (pintype "passive"))
    )
    (net (code "125") (name "unconnected-(IN4C-O-PadO2)") (class "Default")
      (node (ref "IN4") (pin "O2") (pinfunction "O_O2") (pintype "passive"))
    )
    (net (code "126") (name "unconnected-(IN5B-O-PadO1)") (class "Default")
      (node (ref "IN5") (pin "O1") (pinfunction "O_O1") (pintype "passive"))
    )
    (net (code "127") (name "unconnected-(IN5C-O-PadO2)") (class "Default")
      (node (ref "IN5") (pin "O2") (pinfunction "O_O2") (pintype "passive"))
    )
    (net (code "128") (name "unconnected-(K_ASS1C-O-PadO2)") (class "Default")
      (node (ref "K_ASS1") (pin "O2") (pinfunction "O_O2") (pintype "passive"))
    )
    (net (code "129") (name "unconnected-(K_ASS1C-P-PadP2)") (class "Default")
      (node (ref "K_ASS1") (pin "P2") (pinfunction "P_P2") (pintype "passive"))
    )
    (net (code "130") (name "unconnected-(K_ASS1C-S-PadS2)") (class "Default")
      (node (ref "K_ASS1") (pin "S2") (pinfunction "S_S2") (pintype "passive"))
    )
    (net (code "131") (name "unconnected-(K_ASS2B-S-PadS1)") (class "Default")
      (node (ref "K_ASS2") (pin "S1") (pinfunction "S_S1") (pintype "passive"))
    )
    (net (code "132") (name "unconnected-(RARR4-Pad5)") (class "Default")
      (node (ref "RARR4") (pin "5") (pinfunction "5_5") (pintype "passive"))
    )
    (net (code "133") (name "unconnected-(TO_VOLUMEB-S-Pad2)") (class "Default")
      (node (ref "TO_VOLUME") (pin "2") (pinfunction "S_2") (pintype "passive"))
    )
    (net (code "134") (name "unconnected-(TO_VOLUMED-S-Pad4)") (class "Default")
      (node (ref "TO_VOLUME") (pin "4") (pinfunction "S_4") (pintype "passive"))
    )
  )
)
